# Signal_Distribution.net
KiCad netlist of a schematic drawn in Altium Designer
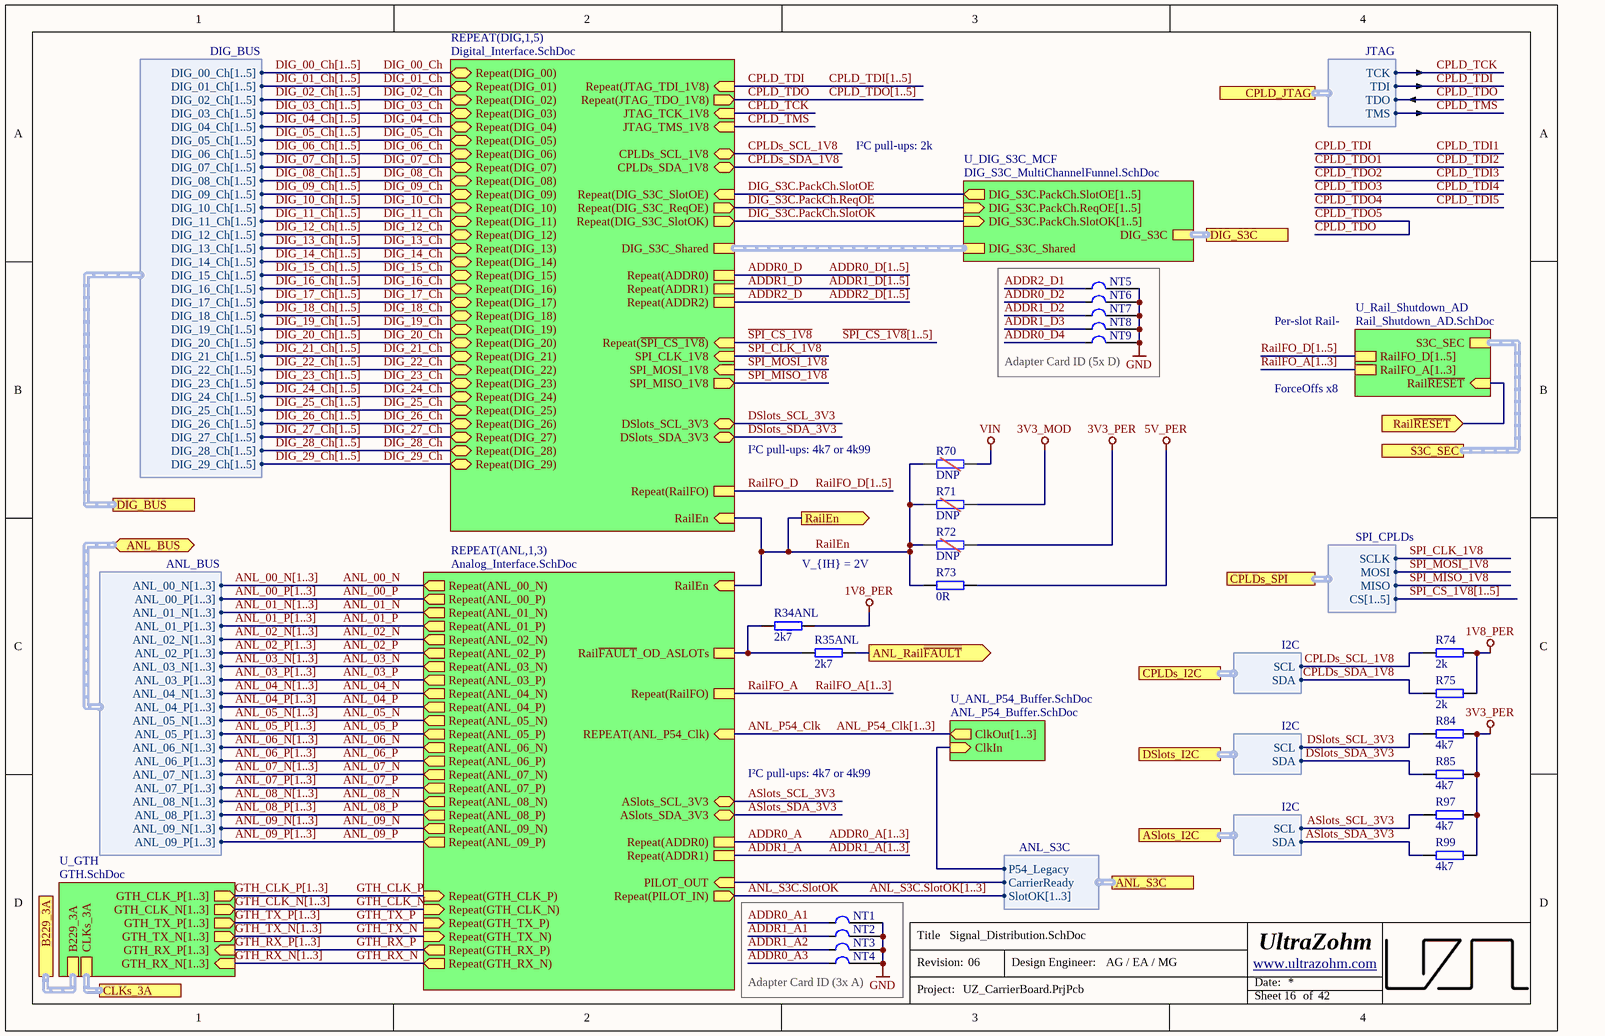
[diagram p0: Signal_Distribution.SchDoc]

(export (version "E")
  (design (tool "Eeschema 10.0.6"))
  (components
    (comp (ref "NT1")
      (value "Net Tie 1 to 1")
      (footprint "1_to_1_NetTie_0.1mm")
      (description "Net Tie 1 to 1. Joins two nets without producing a DRC error or renaming one of the nets")
      (fields (field (name "CREATED BY") "MGeier"))
      (libsource (lib "user") (part "NetTie_1_to_1_small"))
    )
    (comp (ref "NT2")
      (value "Net Tie 1 to 1")
      (footprint "1_to_1_NetTie_0.1mm")
      (description "Net Tie 1 to 1. Joins two nets without producing a DRC error or renaming one of the nets")
      (fields (field (name "CREATED BY") "MGeier"))
      (libsource (lib "user") (part "NetTie_1_to_1_small"))
    )
    (comp (ref "NT3")
      (value "Net Tie 1 to 1")
      (footprint "1_to_1_NetTie_0.1mm")
      (description "Net Tie 1 to 1. Joins two nets without producing a DRC error or renaming one of the nets")
      (fields (field (name "CREATED BY") "MGeier"))
      (libsource (lib "user") (part "NetTie_1_to_1_small"))
    )
    (comp (ref "NT4")
      (value "Net Tie 1 to 1")
      (footprint "1_to_1_NetTie_0.1mm")
      (description "Net Tie 1 to 1. Joins two nets without producing a DRC error or renaming one of the nets")
      (fields (field (name "CREATED BY") "MGeier"))
      (libsource (lib "user") (part "NetTie_1_to_1_small"))
    )
    (comp (ref "NT5")
      (value "Net Tie 1 to 1")
      (footprint "1_to_1_NetTie_0.1mm")
      (description "Net Tie 1 to 1. Joins two nets without producing a DRC error or renaming one of the nets")
      (fields (field (name "CREATED BY") "MGeier"))
      (libsource (lib "user") (part "NetTie_1_to_1_small"))
    )
    (comp (ref "NT6")
      (value "Net Tie 1 to 1")
      (footprint "1_to_1_NetTie_0.1mm")
      (description "Net Tie 1 to 1. Joins two nets without producing a DRC error or renaming one of the nets")
      (fields (field (name "CREATED BY") "MGeier"))
      (libsource (lib "user") (part "NetTie_1_to_1_small"))
    )
    (comp (ref "NT7")
      (value "Net Tie 1 to 1")
      (footprint "1_to_1_NetTie_0.1mm")
      (description "Net Tie 1 to 1. Joins two nets without producing a DRC error or renaming one of the nets")
      (fields (field (name "CREATED BY") "MGeier"))
      (libsource (lib "user") (part "NetTie_1_to_1_small"))
    )
    (comp (ref "NT8")
      (value "Net Tie 1 to 1")
      (footprint "1_to_1_NetTie_0.1mm")
      (description "Net Tie 1 to 1. Joins two nets without producing a DRC error or renaming one of the nets")
      (fields (field (name "CREATED BY") "MGeier"))
      (libsource (lib "user") (part "NetTie_1_to_1_small"))
    )
    (comp (ref "NT9")
      (value "Net Tie 1 to 1")
      (footprint "1_to_1_NetTie_0.1mm")
      (description "Net Tie 1 to 1. Joins two nets without producing a DRC error or renaming one of the nets")
      (fields (field (name "CREATED BY") "MGeier"))
      (libsource (lib "user") (part "NetTie_1_to_1_small"))
    )
    (comp (ref "R34ANL")
      (value "2k7")
      (footprint "R_0603_TE")
      (description "Generic resistor")
      (fields
        (field (name "MANUFACTURER PART NUMBER") "UZgen_R_0603_2k7")
        (field (name "MANUFACTURER") "UZgen")
        (field (name "CREATED FROM") "UZgenTool")
      )
      (libsource (lib "user") (part "RES"))
    )
    (comp (ref "R35ANL")
      (value "2k7")
      (footprint "R_0603_TE")
      (description "Generic resistor")
      (fields
        (field (name "MANUFACTURER PART NUMBER") "UZgen_R_0603_2k7")
        (field (name "MANUFACTURER") "UZgen")
        (field (name "CREATED FROM") "UZgenTool")
      )
      (libsource (lib "user") (part "RES"))
    )
    (comp (ref "R70")
      (value "DNP")
      (footprint "R_1206_TE-DNP")
      (description "Generic resistor (DNP)")
      (fields
        (field (name "MANUFACTURER PART NUMBER") "UZgen_R_1206_DNP")
        (field (name "MANUFACTURER") "UZgen")
        (field (name "CREATED FROM") "UZgenTool")
      )
      (libsource (lib "user") (part "RES-DNP"))
    )
    (comp (ref "R71")
      (value "DNP")
      (footprint "R_1206_TE-DNP")
      (description "Generic resistor (DNP)")
      (fields
        (field (name "MANUFACTURER PART NUMBER") "UZgen_R_1206_DNP")
        (field (name "MANUFACTURER") "UZgen")
        (field (name "CREATED FROM") "UZgenTool")
      )
      (libsource (lib "user") (part "RES-DNP"))
    )
    (comp (ref "R72")
      (value "DNP")
      (footprint "R_1206_TE-DNP")
      (description "Generic resistor (DNP)")
      (fields
        (field (name "MANUFACTURER PART NUMBER") "UZgen_R_1206_DNP")
        (field (name "MANUFACTURER") "UZgen")
        (field (name "CREATED FROM") "UZgenTool")
      )
      (libsource (lib "user") (part "RES-DNP"))
    )
    (comp (ref "R73")
      (value "0R")
      (footprint "R_1206_TE")
      (description "Generic resistor")
      (fields
        (field (name "MANUFACTURER PART NUMBER") "UZgen_R_1206_0R")
        (field (name "MANUFACTURER") "UZgen")
        (field (name "CREATED FROM") "UZgenTool")
      )
      (libsource (lib "user") (part "RES"))
    )
    (comp (ref "R74")
      (value "2k")
      (footprint "R_0603_TE")
      (description "Generic resistor")
      (fields
        (field (name "MANUFACTURER PART NUMBER") "UZgen_R_0603_2k")
        (field (name "MANUFACTURER") "UZgen")
        (field (name "CREATED FROM") "UZgenTool")
      )
      (libsource (lib "user") (part "RES"))
    )
    (comp (ref "R75")
      (value "2k")
      (footprint "R_0603_TE")
      (description "Generic resistor")
      (fields
        (field (name "MANUFACTURER PART NUMBER") "UZgen_R_0603_2k")
        (field (name "MANUFACTURER") "UZgen")
        (field (name "CREATED FROM") "UZgenTool")
      )
      (libsource (lib "user") (part "RES"))
    )
    (comp (ref "R84")
      (value "4k7")
      (footprint "R_0603_TE")
      (description "Generic resistor")
      (fields
        (field (name "MANUFACTURER PART NUMBER") "UZgen_R_0603_4k7")
        (field (name "MANUFACTURER") "UZgen")
        (field (name "CREATED FROM") "UZgenTool")
      )
      (libsource (lib "user") (part "RES"))
    )
    (comp (ref "R85")
      (value "4k7")
      (footprint "R_0603_TE")
      (description "Generic resistor")
      (fields
        (field (name "MANUFACTURER PART NUMBER") "UZgen_R_0603_4k7")
        (field (name "MANUFACTURER") "UZgen")
        (field (name "CREATED FROM") "UZgenTool")
      )
      (libsource (lib "user") (part "RES"))
    )
    (comp (ref "R97")
      (value "4k7")
      (footprint "R_0603_TE")
      (description "Generic resistor")
      (fields
        (field (name "MANUFACTURER PART NUMBER") "UZgen_R_0603_4k7")
        (field (name "MANUFACTURER") "UZgen")
        (field (name "CREATED FROM") "UZgenTool")
      )
      (libsource (lib "user") (part "RES"))
    )
    (comp (ref "R99")
      (value "4k7")
      (footprint "R_0603_TE")
      (description "Generic resistor")
      (fields
        (field (name "MANUFACTURER PART NUMBER") "UZgen_R_0603_4k7")
        (field (name "MANUFACTURER") "UZgen")
        (field (name "CREATED FROM") "UZgenTool")
      )
      (libsource (lib "user") (part "RES"))
    )
  )
  (nets
    (net (code "266") (name "/ADDR0_A1") (class "Default")
      (node (ref "NT1") (pin "1") (pinfunction "1_1") (pintype "passive"))
    )
    (net (code "267") (name "/ADDR0_A3") (class "Default")
      (node (ref "NT4") (pin "1") (pinfunction "1_1") (pintype "passive"))
    )
    (net (code "270") (name "/ADDR0_D2") (class "Default")
      (node (ref "NT6") (pin "1") (pinfunction "1_1") (pintype "passive"))
    )
    (net (code "271") (name "/ADDR0_D4") (class "Default")
      (node (ref "NT9") (pin "1") (pinfunction "1_1") (pintype "passive"))
    )
    (net (code "274") (name "/ADDR1_A1") (class "Default")
      (node (ref "NT2") (pin "1") (pinfunction "1_1") (pintype "passive"))
    )
    (net (code "275") (name "/ADDR1_A2") (class "Default")
      (node (ref "NT3") (pin "1") (pinfunction "1_1") (pintype "passive"))
    )
    (net (code "278") (name "/ADDR1_D2") (class "Default")
      (node (ref "NT7") (pin "1") (pinfunction "1_1") (pintype "passive"))
    )
    (net (code "279") (name "/ADDR1_D3") (class "Default")
      (node (ref "NT8") (pin "1") (pinfunction "1_1") (pintype "passive"))
    )
    (net (code "282") (name "/ADDR2_D1") (class "Default")
      (node (ref "NT5") (pin "1") (pinfunction "1_1") (pintype "passive"))
    )
    (net (code "326") (name "/ANL_Rail~{FAULT}") (class "Default")
      (node (ref "R35ANL") (pin "2") (pinfunction "2_2") (pintype "passive"))
    )
    (net (code "329") (name "/ASlots_SCL_3V3") (class "Default")
      (node (ref "R97") (pin "1") (pinfunction "1_1") (pintype "passive"))
    )
    (net (code "330") (name "/ASlots_SDA_3V3") (class "Default")
      (node (ref "R99") (pin "1") (pinfunction "1_1") (pintype "passive"))
    )
    (net (code "343") (name "/CPLDs_SCL_1V8") (class "Default")
      (node (ref "R74") (pin "1") (pinfunction "1_1") (pintype "passive"))
    )
    (net (code "344") (name "/CPLDs_SDA_1V8") (class "Default")
      (node (ref "R75") (pin "1") (pinfunction "1_1") (pintype "passive"))
    )
    (net (code "414") (name "/DSlots_SCL_3V3") (class "Default")
      (node (ref "R84") (pin "1") (pinfunction "1_1") (pintype "passive"))
    )
    (net (code "415") (name "/DSlots_SDA_3V3") (class "Default")
      (node (ref "R85") (pin "1") (pinfunction "1_1") (pintype "passive"))
    )
    (net (code "429") (name "/RailEn") (class "Default")
      (node (ref "R70") (pin "1") (pinfunction "1_1") (pintype "passive"))
      (node (ref "R71") (pin "1") (pinfunction "1_1") (pintype "passive"))
      (node (ref "R72") (pin "1") (pinfunction "1_1") (pintype "passive"))
      (node (ref "R73") (pin "1") (pinfunction "1_1") (pintype "passive"))
    )
    (net (code "434") (name "/Rail~{FAULT}_OD_ASLOTs") (class "Default")
      (node (ref "R34ANL") (pin "1") (pinfunction "1_1") (pintype "passive"))
      (node (ref "R35ANL") (pin "1") (pinfunction "1_1") (pintype "passive"))
    )
    (net (code "448") (name "1V8_PER") (class "Default")
      (node (ref "R34ANL") (pin "2") (pinfunction "2_2") (pintype "passive"))
      (node (ref "R74") (pin "2") (pinfunction "2_2") (pintype "passive"))
      (node (ref "R75") (pin "2") (pinfunction "2_2") (pintype "passive"))
    )
    (net (code "449") (name "3V3_MOD") (class "Default")
      (node (ref "R71") (pin "2") (pinfunction "2_2") (pintype "passive"))
    )
    (net (code "450") (name "3V3_PER") (class "Default")
      (node (ref "R72") (pin "2") (pinfunction "2_2") (pintype "passive"))
      (node (ref "R84") (pin "2") (pinfunction "2_2") (pintype "passive"))
      (node (ref "R85") (pin "2") (pinfunction "2_2") (pintype "passive"))
      (node (ref "R97") (pin "2") (pinfunction "2_2") (pintype "passive"))
      (node (ref "R99") (pin "2") (pinfunction "2_2") (pintype "passive"))
    )
    (net (code "451") (name "5V_PER") (class "Default")
      (node (ref "R73") (pin "2") (pinfunction "2_2") (pintype "passive"))
    )
    (net (code "452") (name "GND") (class "Default")
      (node (ref "NT1") (pin "2") (pinfunction "2_2") (pintype "passive"))
      (node (ref "NT2") (pin "2") (pinfunction "2_2") (pintype "passive"))
      (node (ref "NT3") (pin "2") (pinfunction "2_2") (pintype "passive"))
      (node (ref "NT4") (pin "2") (pinfunction "2_2") (pintype "passive"))
      (node (ref "NT5") (pin "2") (pinfunction "2_2") (pintype "passive"))
      (node (ref "NT6") (pin "2") (pinfunction "2_2") (pintype "passive"))
      (node (ref "NT7") (pin "2") (pinfunction "2_2") (pintype "passive"))
      (node (ref "NT8") (pin "2") (pinfunction "2_2") (pintype "passive"))
      (node (ref "NT9") (pin "2") (pinfunction "2_2") (pintype "passive"))
    )
    (net (code "453") (name "VIN") (class "Default")
      (node (ref "R70") (pin "2") (pinfunction "2_2") (pintype "passive"))
    )
  )
)
